# Measurements.net
KiCad netlist of a schematic drawn in Altium Designer
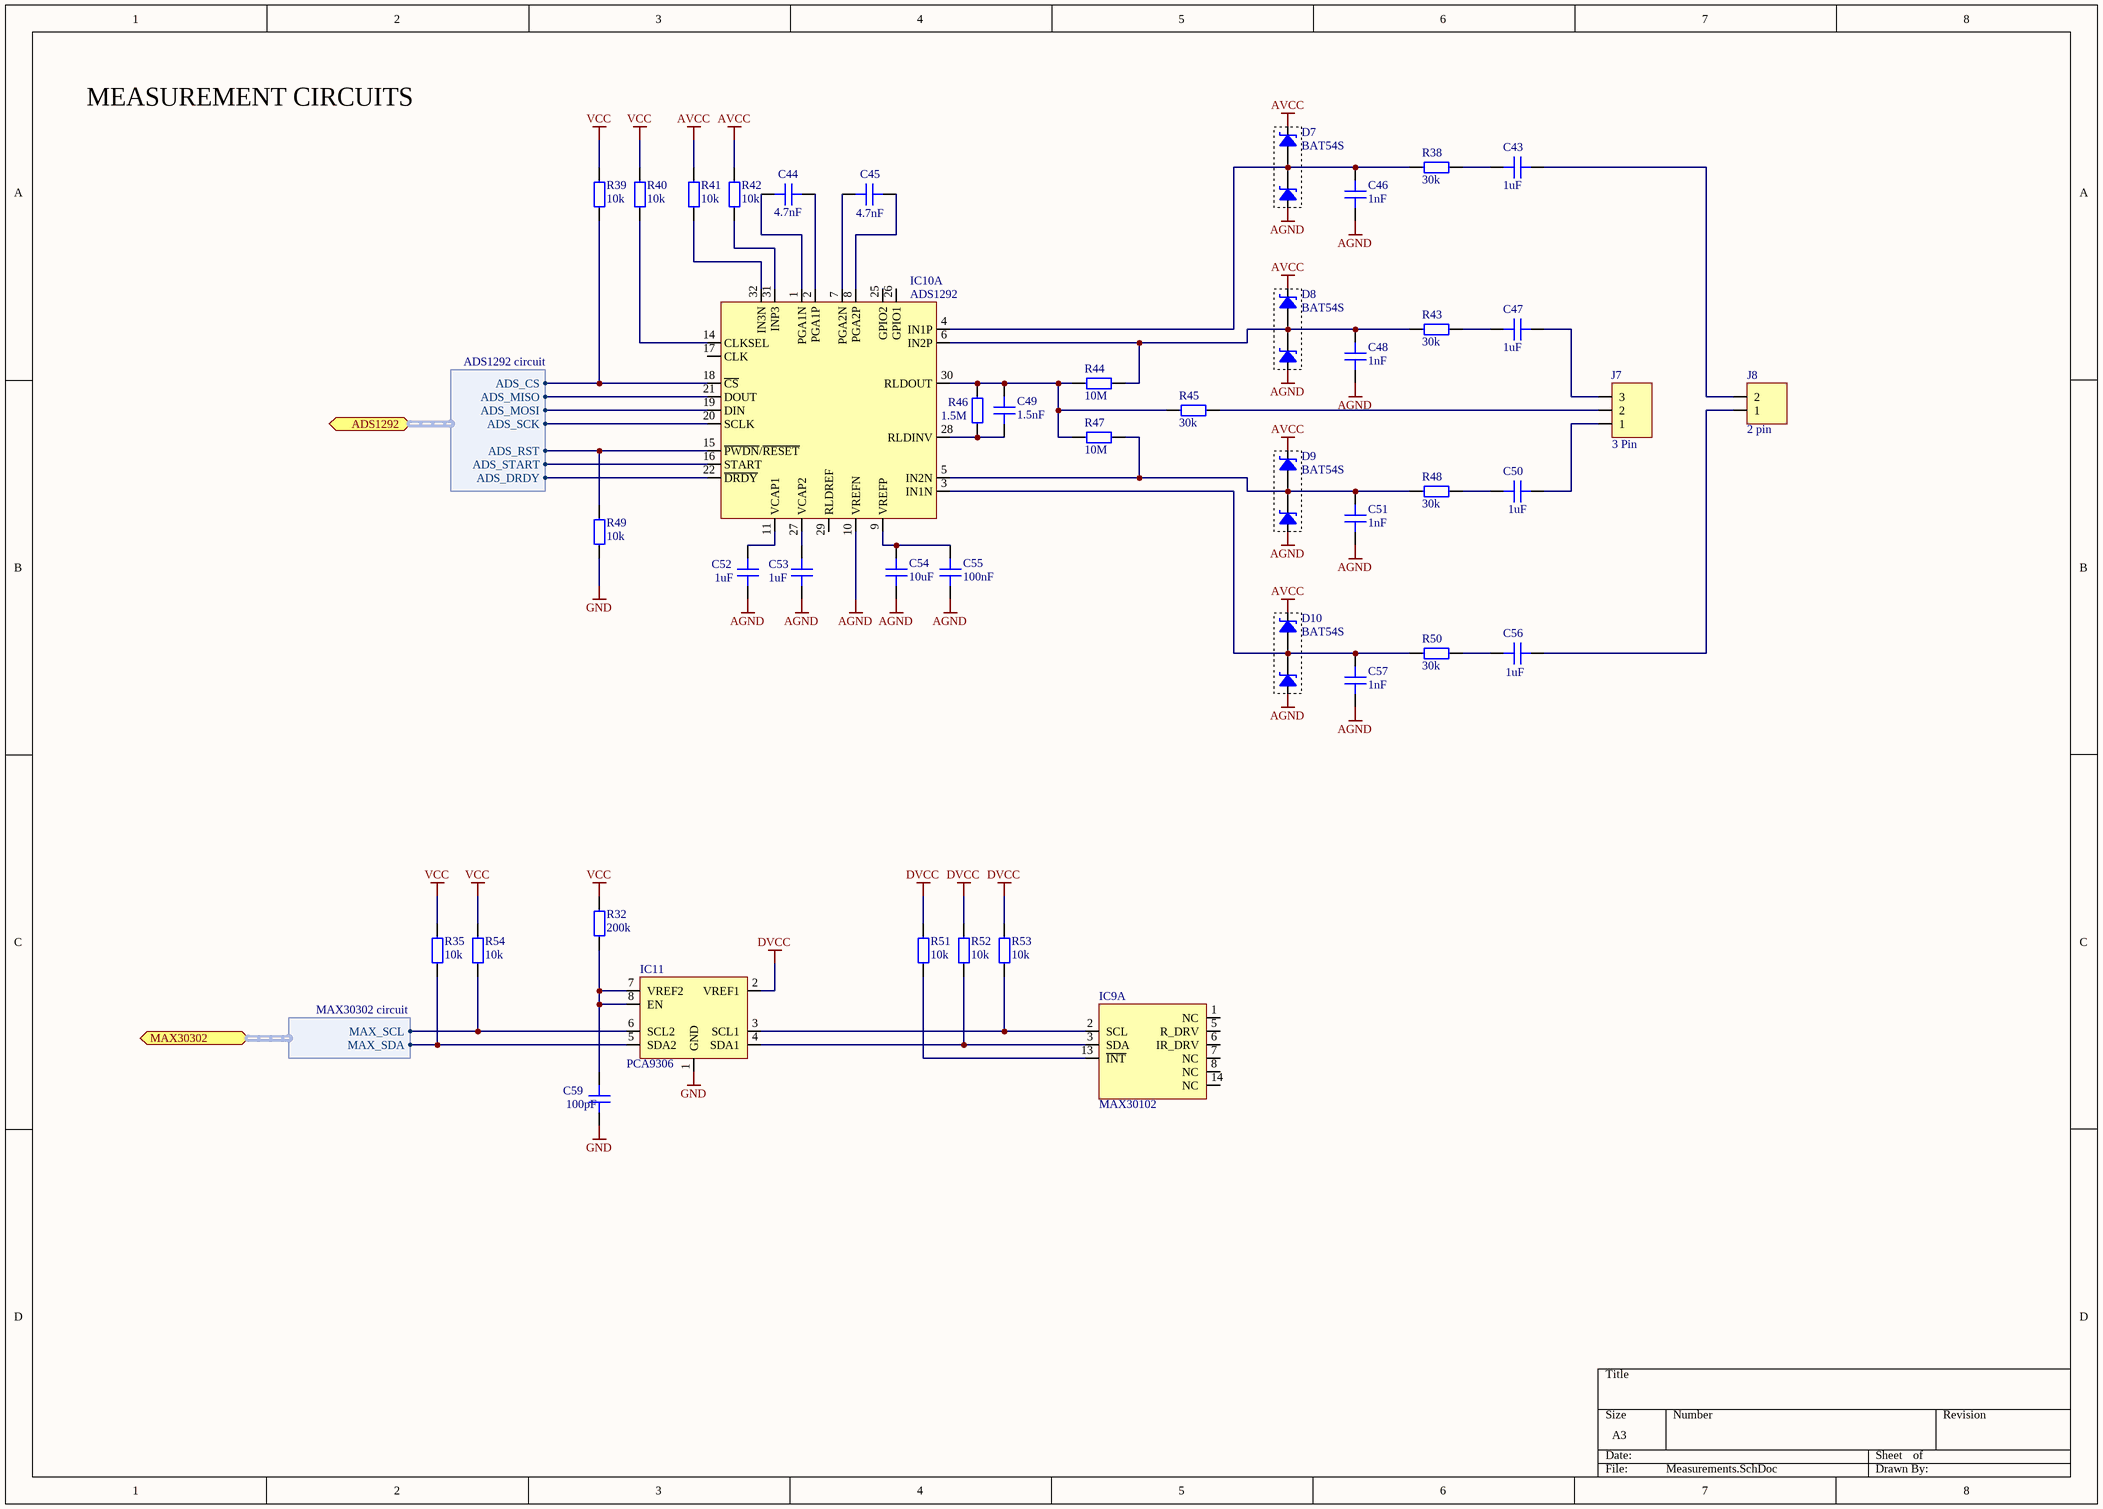
[diagram p0: Measurements.SchDoc]

(export (version "E")
  (design (tool "Eeschema 10.0.6"))
  (components
    (comp (ref "C43")
      (value "1uF")
      (footprint "CAP 0603")
      (description "SMT Capacitor")
      (libsource (lib "Passive") (part "Capacitor"))
    )
    (comp (ref "C44")
      (value "4.7nF")
      (footprint "CAP 0603")
      (description "SMT Capacitor")
      (libsource (lib "Passive") (part "Capacitor"))
    )
    (comp (ref "C45")
      (value "4.7nF")
      (footprint "CAP 0603")
      (description "SMT Capacitor")
      (libsource (lib "Passive") (part "Capacitor"))
    )
    (comp (ref "C46")
      (value "1nF")
      (footprint "CAP 0603")
      (description "SMT Capacitor")
      (libsource (lib "Passive") (part "Capacitor"))
    )
    (comp (ref "C47")
      (value "1uF")
      (footprint "CAP 0603")
      (description "SMT Capacitor")
      (libsource (lib "Passive") (part "Capacitor"))
    )
    (comp (ref "C48")
      (value "1nF")
      (footprint "CAP 0603")
      (description "SMT Capacitor")
      (libsource (lib "Passive") (part "Capacitor"))
    )
    (comp (ref "C49")
      (value "1.5nF")
      (footprint "CAP 0603")
      (description "SMT Capacitor")
      (libsource (lib "Passive") (part "Capacitor"))
    )
    (comp (ref "C50")
      (value "1uF")
      (footprint "CAP 0603")
      (description "SMT Capacitor")
      (libsource (lib "Passive") (part "Capacitor"))
    )
    (comp (ref "C51")
      (value "1nF")
      (footprint "CAP 0603")
      (description "SMT Capacitor")
      (libsource (lib "Passive") (part "Capacitor"))
    )
    (comp (ref "C52")
      (value "1uF")
      (footprint "CAP 0603")
      (description "SMT Capacitor")
      (libsource (lib "Passive") (part "Capacitor"))
    )
    (comp (ref "C53")
      (value "1uF")
      (footprint "CAP 0603")
      (description "SMT Capacitor")
      (libsource (lib "Passive") (part "Capacitor"))
    )
    (comp (ref "C54")
      (value "10uF")
      (footprint "CAP 0603")
      (description "SMT Capacitor")
      (libsource (lib "Passive") (part "Capacitor"))
    )
    (comp (ref "C55")
      (value "100nF")
      (footprint "CAP 0603")
      (description "SMT Capacitor")
      (libsource (lib "Passive") (part "Capacitor"))
    )
    (comp (ref "C56")
      (value "1uF")
      (footprint "CAP 0603")
      (description "SMT Capacitor")
      (libsource (lib "Passive") (part "Capacitor"))
    )
    (comp (ref "C57")
      (value "1nF")
      (footprint "CAP 0603")
      (description "SMT Capacitor")
      (libsource (lib "Passive") (part "Capacitor"))
    )
    (comp (ref "C59")
      (value "100pF")
      (footprint "CAP 0603")
      (description "SMT Capacitor")
      (libsource (lib "Passive") (part "Capacitor"))
    )
    (comp (ref "D7")
      (value "BAT54S")
      (footprint "SOT23")
      (description "Schottky barrier diodes")
      (libsource (lib "Diodes") (part "BAT54S"))
    )
    (comp (ref "D8")
      (value "BAT54S")
      (footprint "SOT23")
      (description "Schottky barrier diodes")
      (libsource (lib "Diodes") (part "BAT54S"))
    )
    (comp (ref "D9")
      (value "BAT54S")
      (footprint "SOT23")
      (description "Schottky barrier diodes")
      (libsource (lib "Diodes") (part "BAT54S"))
    )
    (comp (ref "D10")
      (value "BAT54S")
      (footprint "SOT23")
      (description "Schottky barrier diodes")
      (libsource (lib "Diodes") (part "BAT54S"))
    )
    (comp (ref "IC9")
      (value "MAX30102")
      (footprint "MAX30102")
      (description "Pulse Oximeter and Heart-Rate Sensor")
      (libsource (lib "IC") (part "MAX30102"))
    )
    (comp (ref "IC10")
      (value "ADS1292")
      (footprint "TQFP40")
      (description "ADS1292IRSMT Analog Front End - AFE Cmplt Lw Pwr Intgrtd AFE for ECG apps")
      (libsource (lib "IC") (part "ADS1292IRSMT"))
    )
    (comp (ref "IC11")
      (value "PCA9306")
      (footprint "SSOP8")
      (description "Dual Bidirectional I2C Bus and SMBus Voltage-Level Translator")
      (libsource (lib "IC") (part "PCA9306"))
    )
    (comp (ref "J7")
      (value "3 Pin")
      (footprint "HDR 1x3 2.54")
      (description "3 pin header, male")
      (libsource (lib "Connectors") (part "3 Pin"))
    )
    (comp (ref "J8")
      (value "2 pin")
      (footprint "HDR 1x2 2.54")
      (description "2 pin header, male")
      (libsource (lib "Connectors") (part "2 pin"))
    )
    (comp (ref "R32")
      (value "200k")
      (footprint "RES 0603")
      (description "SMDResistor")
      (libsource (lib "Passive") (part "Resistor"))
    )
    (comp (ref "R35")
      (value "10k")
      (footprint "RES 0603")
      (description "SMDResistor")
      (libsource (lib "Passive") (part "Resistor"))
    )
    (comp (ref "R38")
      (value "30k")
      (footprint "RES 0603")
      (description "SMDResistor")
      (libsource (lib "Passive") (part "Resistor"))
    )
    (comp (ref "R39")
      (value "10k")
      (footprint "RES 0603")
      (description "SMDResistor")
      (libsource (lib "Passive") (part "Resistor"))
    )
    (comp (ref "R40")
      (value "10k")
      (footprint "RES 0603")
      (description "SMDResistor")
      (libsource (lib "Passive") (part "Resistor"))
    )
    (comp (ref "R41")
      (value "10k")
      (footprint "RES 0603")
      (description "SMDResistor")
      (libsource (lib "Passive") (part "Resistor"))
    )
    (comp (ref "R42")
      (value "10k")
      (footprint "RES 0603")
      (description "SMDResistor")
      (libsource (lib "Passive") (part "Resistor"))
    )
    (comp (ref "R43")
      (value "30k")
      (footprint "RES 0603")
      (description "SMDResistor")
      (libsource (lib "Passive") (part "Resistor"))
    )
    (comp (ref "R44")
      (value "10M")
      (footprint "RES 0603")
      (description "SMDResistor")
      (libsource (lib "Passive") (part "Resistor"))
    )
    (comp (ref "R45")
      (value "30k")
      (footprint "RES 0603")
      (description "SMDResistor")
      (libsource (lib "Passive") (part "Resistor"))
    )
    (comp (ref "R46")
      (value "1.5M")
      (footprint "RES 0603")
      (description "SMDResistor")
      (libsource (lib "Passive") (part "Resistor"))
    )
    (comp (ref "R47")
      (value "10M")
      (footprint "RES 0603")
      (description "SMDResistor")
      (libsource (lib "Passive") (part "Resistor"))
    )
    (comp (ref "R48")
      (value "30k")
      (footprint "RES 0603")
      (description "SMDResistor")
      (libsource (lib "Passive") (part "Resistor"))
    )
    (comp (ref "R49")
      (value "10k")
      (footprint "RES 0603")
      (description "SMDResistor")
      (libsource (lib "Passive") (part "Resistor"))
    )
    (comp (ref "R50")
      (value "30k")
      (footprint "RES 0603")
      (description "SMDResistor")
      (libsource (lib "Passive") (part "Resistor"))
    )
    (comp (ref "R51")
      (value "10k")
      (footprint "RES 0603")
      (description "SMDResistor")
      (libsource (lib "Passive") (part "Resistor"))
    )
    (comp (ref "R52")
      (value "10k")
      (footprint "RES 0603")
      (description "SMDResistor")
      (libsource (lib "Passive") (part "Resistor"))
    )
    (comp (ref "R53")
      (value "10k")
      (footprint "RES 0603")
      (description "SMDResistor")
      (libsource (lib "Passive") (part "Resistor"))
    )
    (comp (ref "R54")
      (value "10k")
      (footprint "RES 0603")
      (description "SMDResistor")
      (libsource (lib "Passive") (part "Resistor"))
    )
  )
  (nets
    (net (code "4") (name "/ADS_CS") (class "Default")
      (node (ref "IC10") (pin "18") (pinfunction "~{CS}_18") (pintype "passive"))
      (node (ref "R39") (pin "1") (pinfunction "1_1") (pintype "passive"))
    )
    (net (code "5") (name "/ADS_DRDY") (class "Default")
      (node (ref "IC10") (pin "22") (pinfunction "~{DRDY}_22") (pintype "passive"))
    )
    (net (code "6") (name "/ADS_MISO") (class "Default")
      (node (ref "IC10") (pin "21") (pinfunction "DOUT_21") (pintype "passive"))
    )
    (net (code "7") (name "/ADS_MOSI") (class "Default")
      (node (ref "IC10") (pin "19") (pinfunction "DIN_19") (pintype "passive"))
    )
    (net (code "8") (name "/ADS_RST") (class "Default")
      (node (ref "IC10") (pin "15") (pinfunction "~{PWDN}/~{RESET}_15") (pintype "passive"))
      (node (ref "R49") (pin "2") (pinfunction "2_2") (pintype "passive"))
    )
    (net (code "9") (name "/ADS_SCK") (class "Default")
      (node (ref "IC10") (pin "20") (pinfunction "SCLK_20") (pintype "passive"))
    )
    (net (code "10") (name "/ADS_START") (class "Default")
      (node (ref "IC10") (pin "16") (pinfunction "START_16") (pintype "passive"))
    )
    (net (code "11") (name "/MAX_SCL") (class "Default")
      (node (ref "IC11") (pin "6") (pinfunction "SCL2_6") (pintype "passive"))
      (node (ref "R54") (pin "1") (pinfunction "1_1") (pintype "passive"))
    )
    (net (code "12") (name "/MAX_SDA") (class "Default")
      (node (ref "IC11") (pin "5") (pinfunction "SDA2_5") (pintype "passive"))
      (node (ref "R35") (pin "1") (pinfunction "1_1") (pintype "passive"))
    )
    (net (code "15") (name "AGND") (class "Default")
      (node (ref "C46") (pin "1") (pinfunction "1_1") (pintype "passive"))
      (node (ref "C48") (pin "1") (pinfunction "1_1") (pintype "passive"))
      (node (ref "C51") (pin "1") (pinfunction "1_1") (pintype "passive"))
      (node (ref "C52") (pin "1") (pinfunction "1_1") (pintype "passive"))
      (node (ref "C53") (pin "1") (pinfunction "1_1") (pintype "passive"))
      (node (ref "C54") (pin "1") (pinfunction "1_1") (pintype "passive"))
      (node (ref "C55") (pin "1") (pinfunction "1_1") (pintype "passive"))
      (node (ref "C57") (pin "1") (pinfunction "1_1") (pintype "passive"))
      (node (ref "D10") (pin "1") (pinfunction "1_1") (pintype "passive"))
      (node (ref "D7") (pin "1") (pinfunction "1_1") (pintype "passive"))
      (node (ref "D8") (pin "1") (pinfunction "1_1") (pintype "passive"))
      (node (ref "D9") (pin "1") (pinfunction "1_1") (pintype "passive"))
      (node (ref "IC10") (pin "10") (pinfunction "VREFN_10") (pintype "passive"))
    )
    (net (code "16") (name "AVCC") (class "Default")
      (node (ref "D10") (pin "2") (pinfunction "2_2") (pintype "passive"))
      (node (ref "D7") (pin "2") (pinfunction "2_2") (pintype "passive"))
      (node (ref "D8") (pin "2") (pinfunction "2_2") (pintype "passive"))
      (node (ref "D9") (pin "2") (pinfunction "2_2") (pintype "passive"))
      (node (ref "R41") (pin "2") (pinfunction "2_2") (pintype "passive"))
      (node (ref "R42") (pin "2") (pinfunction "2_2") (pintype "passive"))
    )
    (net (code "17") (name "DVCC") (class "Default")
      (node (ref "IC11") (pin "2") (pinfunction "VREF1_2") (pintype "passive"))
      (node (ref "R51") (pin "2") (pinfunction "2_2") (pintype "passive"))
      (node (ref "R52") (pin "2") (pinfunction "2_2") (pintype "passive"))
      (node (ref "R53") (pin "2") (pinfunction "2_2") (pintype "passive"))
    )
    (net (code "18") (name "GND") (class "Default")
      (node (ref "C59") (pin "1") (pinfunction "1_1") (pintype "passive"))
      (node (ref "IC11") (pin "1") (pinfunction "GND_1") (pintype "passive"))
      (node (ref "R49") (pin "1") (pinfunction "1_1") (pintype "passive"))
    )
    (net (code "19") (name "Net-(C43-Pad1)") (class "Default")
      (node (ref "C43") (pin "1") (pinfunction "1_1") (pintype "passive"))
      (node (ref "J8") (pin "2") (pinfunction "2_2") (pintype "passive"))
    )
    (net (code "20") (name "Net-(C43-Pad2)") (class "Default")
      (node (ref "C43") (pin "2") (pinfunction "2_2") (pintype "passive"))
      (node (ref "R38") (pin "1") (pinfunction "1_1") (pintype "passive"))
    )
    (net (code "21") (name "Net-(C47-Pad1)") (class "Default")
      (node (ref "C47") (pin "1") (pinfunction "1_1") (pintype "passive"))
      (node (ref "J7") (pin "3") (pinfunction "3_3") (pintype "passive"))
    )
    (net (code "22") (name "Net-(C47-Pad2)") (class "Default")
      (node (ref "C47") (pin "2") (pinfunction "2_2") (pintype "passive"))
      (node (ref "R43") (pin "1") (pinfunction "1_1") (pintype "passive"))
    )
    (net (code "23") (name "Net-(C50-Pad1)") (class "Default")
      (node (ref "C50") (pin "1") (pinfunction "1_1") (pintype "passive"))
      (node (ref "J7") (pin "1") (pinfunction "1_1") (pintype "passive"))
    )
    (net (code "24") (name "Net-(C50-Pad2)") (class "Default")
      (node (ref "C50") (pin "2") (pinfunction "2_2") (pintype "passive"))
      (node (ref "R48") (pin "1") (pinfunction "1_1") (pintype "passive"))
    )
    (net (code "25") (name "Net-(C56-Pad1)") (class "Default")
      (node (ref "C56") (pin "1") (pinfunction "1_1") (pintype "passive"))
      (node (ref "J8") (pin "1") (pinfunction "1_1") (pintype "passive"))
    )
    (net (code "26") (name "Net-(C56-Pad2)") (class "Default")
      (node (ref "C56") (pin "2") (pinfunction "2_2") (pintype "passive"))
      (node (ref "R50") (pin "1") (pinfunction "1_1") (pintype "passive"))
    )
    (net (code "27") (name "Net-(IC9A-~{INT})") (class "Default")
      (node (ref "IC9") (pin "13") (pinfunction "~{INT}_13") (pintype "passive"))
      (node (ref "R51") (pin "1") (pinfunction "1_1") (pintype "passive"))
    )
    (net (code "28") (name "Net-(IC10A-CLKSEL)") (class "Default")
      (node (ref "IC10") (pin "14") (pinfunction "CLKSEL_14") (pintype "passive"))
      (node (ref "R40") (pin "1") (pinfunction "1_1") (pintype "passive"))
    )
    (net (code "29") (name "Net-(IC10A-IN1N)") (class "Default")
      (node (ref "C57") (pin "2") (pinfunction "2_2") (pintype "passive"))
      (node (ref "D10") (pin "3") (pinfunction "3_3") (pintype "passive"))
      (node (ref "IC10") (pin "3") (pinfunction "IN1N_3") (pintype "passive"))
      (node (ref "R50") (pin "2") (pinfunction "2_2") (pintype "passive"))
    )
    (net (code "30") (name "Net-(IC10A-IN1P)") (class "Default")
      (node (ref "C46") (pin "2") (pinfunction "2_2") (pintype "passive"))
      (node (ref "D7") (pin "3") (pinfunction "3_3") (pintype "passive"))
      (node (ref "IC10") (pin "4") (pinfunction "IN1P_4") (pintype "passive"))
      (node (ref "R38") (pin "2") (pinfunction "2_2") (pintype "passive"))
    )
    (net (code "31") (name "Net-(IC10A-IN2N)") (class "Default")
      (node (ref "C51") (pin "2") (pinfunction "2_2") (pintype "passive"))
      (node (ref "D9") (pin "3") (pinfunction "3_3") (pintype "passive"))
      (node (ref "IC10") (pin "5") (pinfunction "IN2N_5") (pintype "passive"))
      (node (ref "R47") (pin "1") (pinfunction "1_1") (pintype "passive"))
      (node (ref "R48") (pin "2") (pinfunction "2_2") (pintype "passive"))
    )
    (net (code "32") (name "Net-(IC10A-IN2P)") (class "Default")
      (node (ref "C48") (pin "2") (pinfunction "2_2") (pintype "passive"))
      (node (ref "D8") (pin "3") (pinfunction "3_3") (pintype "passive"))
      (node (ref "IC10") (pin "6") (pinfunction "IN2P_6") (pintype "passive"))
      (node (ref "R43") (pin "2") (pinfunction "2_2") (pintype "passive"))
      (node (ref "R44") (pin "1") (pinfunction "1_1") (pintype "passive"))
    )
    (net (code "33") (name "Net-(IC10A-IN3N)") (class "Default")
      (node (ref "IC10") (pin "32") (pinfunction "IN3N_32") (pintype "passive"))
      (node (ref "R41") (pin "1") (pinfunction "1_1") (pintype "passive"))
    )
    (net (code "34") (name "Net-(IC10A-INP3)") (class "Default")
      (node (ref "IC10") (pin "31") (pinfunction "INP3_31") (pintype "passive"))
      (node (ref "R42") (pin "1") (pinfunction "1_1") (pintype "passive"))
    )
    (net (code "35") (name "Net-(IC10A-PGA1N)") (class "Default")
      (node (ref "C44") (pin "1") (pinfunction "1_1") (pintype "passive"))
      (node (ref "IC10") (pin "1") (pinfunction "PGA1N_1") (pintype "passive"))
    )
    (net (code "36") (name "Net-(IC10A-PGA1P)") (class "Default")
      (node (ref "C44") (pin "2") (pinfunction "2_2") (pintype "passive"))
      (node (ref "IC10") (pin "2") (pinfunction "PGA1P_2") (pintype "passive"))
    )
    (net (code "37") (name "Net-(IC10A-PGA2N)") (class "Default")
      (node (ref "C45") (pin "1") (pinfunction "1_1") (pintype "passive"))
      (node (ref "IC10") (pin "7") (pinfunction "PGA2N_7") (pintype "passive"))
    )
    (net (code "38") (name "Net-(IC10A-PGA2P)") (class "Default")
      (node (ref "C45") (pin "2") (pinfunction "2_2") (pintype "passive"))
      (node (ref "IC10") (pin "8") (pinfunction "PGA2P_8") (pintype "passive"))
    )
    (net (code "39") (name "Net-(IC10A-RLDINV)") (class "Default")
      (node (ref "C49") (pin "1") (pinfunction "1_1") (pintype "passive"))
      (node (ref "IC10") (pin "28") (pinfunction "RLDINV_28") (pintype "passive"))
      (node (ref "R46") (pin "1") (pinfunction "1_1") (pintype "passive"))
    )
    (net (code "40") (name "Net-(IC10A-RLDOUT)") (class "Default")
      (node (ref "C49") (pin "2") (pinfunction "2_2") (pintype "passive"))
      (node (ref "IC10") (pin "30") (pinfunction "RLDOUT_30") (pintype "passive"))
      (node (ref "R44") (pin "2") (pinfunction "2_2") (pintype "passive"))
      (node (ref "R45") (pin "2") (pinfunction "2_2") (pintype "passive"))
      (node (ref "R46") (pin "2") (pinfunction "2_2") (pintype "passive"))
      (node (ref "R47") (pin "2") (pinfunction "2_2") (pintype "passive"))
    )
    (net (code "41") (name "Net-(IC10A-VCAP1)") (class "Default")
      (node (ref "C52") (pin "2") (pinfunction "2_2") (pintype "passive"))
      (node (ref "IC10") (pin "11") (pinfunction "VCAP1_11") (pintype "passive"))
    )
    (net (code "42") (name "Net-(IC10A-VCAP2)") (class "Default")
      (node (ref "C53") (pin "2") (pinfunction "2_2") (pintype "passive"))
      (node (ref "IC10") (pin "27") (pinfunction "VCAP2_27") (pintype "passive"))
    )
    (net (code "43") (name "Net-(IC10A-VREFP)") (class "Default")
      (node (ref "C54") (pin "2") (pinfunction "2_2") (pintype "passive"))
      (node (ref "C55") (pin "2") (pinfunction "2_2") (pintype "passive"))
      (node (ref "IC10") (pin "9") (pinfunction "VREFP_9") (pintype "passive"))
    )
    (net (code "44") (name "Net-(IC11-EN)") (class "Default")
      (node (ref "C59") (pin "2") (pinfunction "2_2") (pintype "passive"))
      (node (ref "IC11") (pin "7") (pinfunction "VREF2_7") (pintype "passive"))
      (node (ref "IC11") (pin "8") (pinfunction "EN_8") (pintype "passive"))
      (node (ref "R32") (pin "1") (pinfunction "1_1") (pintype "passive"))
    )
    (net (code "45") (name "Net-(IC11-SCL1)") (class "Default")
      (node (ref "IC11") (pin "3") (pinfunction "SCL1_3") (pintype "passive"))
      (node (ref "IC9") (pin "2") (pinfunction "SCL_2") (pintype "passive"))
      (node (ref "R53") (pin "1") (pinfunction "1_1") (pintype "passive"))
    )
    (net (code "46") (name "Net-(IC11-SDA1)") (class "Default")
      (node (ref "IC11") (pin "4") (pinfunction "SDA1_4") (pintype "passive"))
      (node (ref "IC9") (pin "3") (pinfunction "SDA_3") (pintype "passive"))
      (node (ref "R52") (pin "1") (pinfunction "1_1") (pintype "passive"))
    )
    (net (code "47") (name "Net-(J7-Pad2)") (class "Default")
      (node (ref "J7") (pin "2") (pinfunction "2_2") (pintype "passive"))
      (node (ref "R45") (pin "1") (pinfunction "1_1") (pintype "passive"))
    )
    (net (code "48") (name "VCC") (class "Default")
      (node (ref "R32") (pin "2") (pinfunction "2_2") (pintype "passive"))
      (node (ref "R35") (pin "2") (pinfunction "2_2") (pintype "passive"))
      (node (ref "R39") (pin "2") (pinfunction "2_2") (pintype "passive"))
      (node (ref "R40") (pin "2") (pinfunction "2_2") (pintype "passive"))
      (node (ref "R54") (pin "2") (pinfunction "2_2") (pintype "passive"))
    )
    (net (code "49") (name "unconnected-(IC9A-IR_DRV-Pad6)") (class "Default")
      (node (ref "IC9") (pin "6") (pinfunction "IR_DRV_6") (pintype "passive"))
    )
    (net (code "50") (name "unconnected-(IC9A-NC-Pad1)") (class "Default")
      (node (ref "IC9") (pin "1") (pinfunction "NC_1") (pintype "passive"))
    )
    (net (code "51") (name "unconnected-(IC9A-NC-Pad7)") (class "Default")
      (node (ref "IC9") (pin "7") (pinfunction "NC_7") (pintype "passive"))
    )
    (net (code "52") (name "unconnected-(IC9A-NC-Pad8)") (class "Default")
      (node (ref "IC9") (pin "8") (pinfunction "NC_8") (pintype "passive"))
    )
    (net (code "53") (name "unconnected-(IC9A-NC-Pad14)") (class "Default")
      (node (ref "IC9") (pin "14") (pinfunction "NC_14") (pintype "passive"))
    )
    (net (code "54") (name "unconnected-(IC9A-R_DRV-Pad5)") (class "Default")
      (node (ref "IC9") (pin "5") (pinfunction "R_DRV_5") (pintype "passive"))
    )
    (net (code "55") (name "unconnected-(IC10A-CLK-Pad17)") (class "Default")
      (node (ref "IC10") (pin "17") (pinfunction "CLK_17") (pintype "passive"))
    )
    (net (code "56") (name "unconnected-(IC10A-GPIO1-Pad26)") (class "Default")
      (node (ref "IC10") (pin "26") (pinfunction "GPIO1_26") (pintype "passive"))
    )
    (net (code "57") (name "unconnected-(IC10A-GPIO2-Pad25)") (class "Default")
      (node (ref "IC10") (pin "25") (pinfunction "GPIO2_25") (pintype "passive"))
    )
    (net (code "58") (name "unconnected-(IC10A-RLDREF-Pad29)") (class "Default")
      (node (ref "IC10") (pin "29") (pinfunction "RLDREF_29") (pintype "passive"))
    )
  )
)
